# od2_redraw.net
KiCad netlist of a schematic drawn in EAGLE
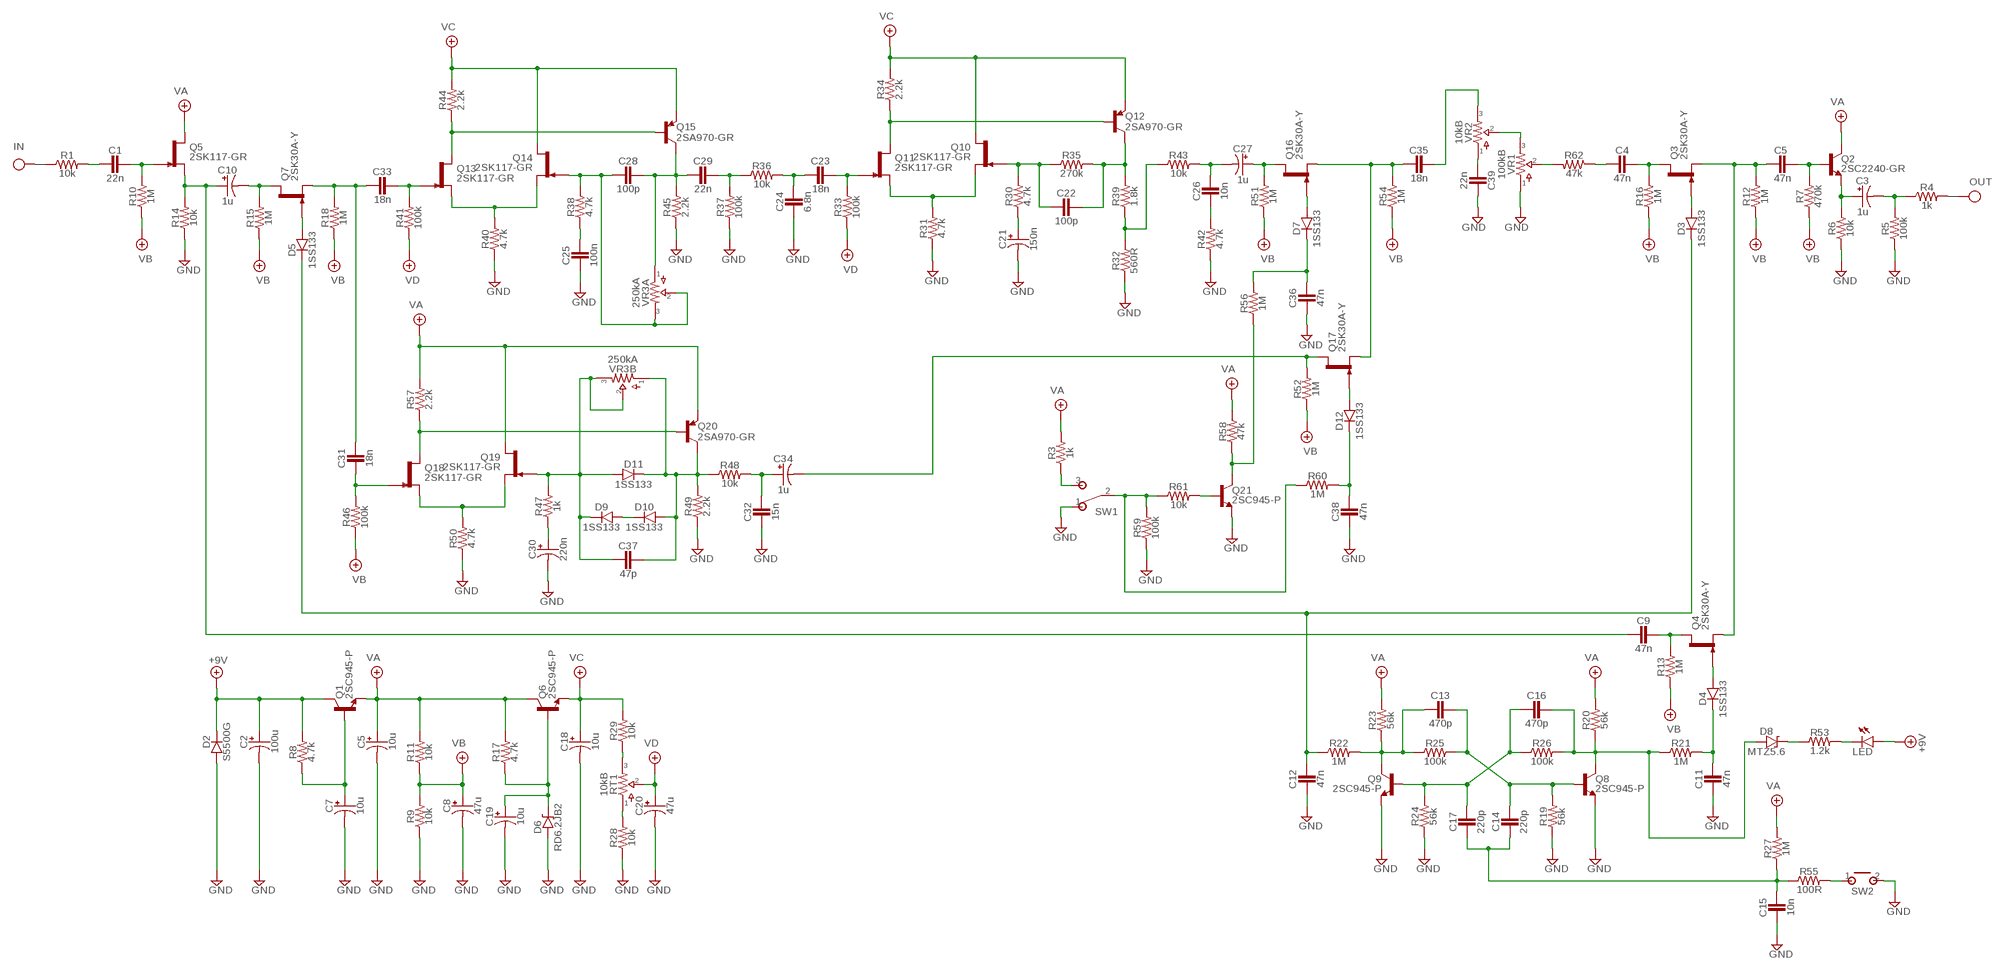
[diagram p0: schematic, sheet 1]

(export (version "E")
  (design (tool "Eeschema 10.0.6"))
  (components
    (comp (ref "C1")
      (value "22n")
      (footprint "eagle-import:BOX_SMALL")
      (libsource (lib "eagle-import") (part "CER/FILMBOX.1"))
    )
    (comp (ref "C2")
      (value "100u")
      (footprint "eagle-import:040_020")
      (libsource (lib "eagle-import") (part "0400"))
    )
    (comp (ref "C3")
      (value "1u")
      (footprint "eagle-import:040_020")
      (libsource (lib "eagle-import") (part "0400"))
    )
    (comp (ref "C4")
      (value "47n")
      (footprint "eagle-import:BOX_SMALL")
      (libsource (lib "eagle-import") (part "CER/FILMBOX.1"))
    )
    (comp (ref "C5")
      (value "10u")
      (footprint "eagle-import:040_020")
      (libsource (lib "eagle-import") (part "0400"))
    )
    (comp (ref "C5 ")
      (value "47n")
      (footprint "eagle-import:BOX_SMALL")
      (libsource (lib "eagle-import") (part "CER/FILMBOX.1"))
    )
    (comp (ref "C7")
      (value "10u")
      (footprint "eagle-import:040_020")
      (libsource (lib "eagle-import") (part "0400"))
    )
    (comp (ref "C8")
      (value "47u")
      (footprint "eagle-import:040_020")
      (libsource (lib "eagle-import") (part "0400"))
    )
    (comp (ref "C9")
      (value "47n")
      (footprint "eagle-import:BOX_SMALL")
      (libsource (lib "eagle-import") (part "CER/FILMBOX.1"))
    )
    (comp (ref "C10")
      (value "1u")
      (footprint "eagle-import:040_020")
      (libsource (lib "eagle-import") (part "0400"))
    )
    (comp (ref "C11")
      (value "47n")
      (footprint "eagle-import:BOX_SMALL")
      (libsource (lib "eagle-import") (part "CER/FILMBOX.1"))
    )
    (comp (ref "C12")
      (value "47n")
      (footprint "eagle-import:BOX_SMALL")
      (libsource (lib "eagle-import") (part "CER/FILMBOX.1"))
    )
    (comp (ref "C13")
      (value "470p")
      (footprint "eagle-import:BOX_SMALL")
      (libsource (lib "eagle-import") (part "CER/FILMBOX.1"))
    )
    (comp (ref "C14")
      (value "220p")
      (footprint "eagle-import:BOX_SMALL")
      (libsource (lib "eagle-import") (part "CER/FILMBOX.1"))
    )
    (comp (ref "C15")
      (value "10n")
      (footprint "eagle-import:BOX_SMALL")
      (libsource (lib "eagle-import") (part "CER/FILMBOX.1"))
    )
    (comp (ref "C16")
      (value "470p")
      (footprint "eagle-import:BOX_SMALL")
      (libsource (lib "eagle-import") (part "CER/FILMBOX.1"))
    )
    (comp (ref "C17")
      (value "220p")
      (footprint "eagle-import:BOX_SMALL")
      (libsource (lib "eagle-import") (part "CER/FILMBOX.1"))
    )
    (comp (ref "C18")
      (value "10u")
      (footprint "eagle-import:040_020")
      (libsource (lib "eagle-import") (part "0400"))
    )
    (comp (ref "C19")
      (value "10u")
      (footprint "eagle-import:040_020")
      (libsource (lib "eagle-import") (part "0400"))
    )
    (comp (ref "C20")
      (value "47u")
      (footprint "eagle-import:040_020")
      (libsource (lib "eagle-import") (part "0400"))
    )
    (comp (ref "C21")
      (value "150n")
      (footprint "eagle-import:040_020")
      (libsource (lib "eagle-import") (part "0400"))
    )
    (comp (ref "C22")
      (value "100p")
      (footprint "eagle-import:BOX_SMALL")
      (libsource (lib "eagle-import") (part "CER/FILMBOX.1"))
    )
    (comp (ref "C23")
      (value "18n")
      (footprint "eagle-import:BOX_SMALL")
      (libsource (lib "eagle-import") (part "CER/FILMBOX.1"))
    )
    (comp (ref "C24")
      (value "6.8n")
      (footprint "eagle-import:BOX_SMALL")
      (libsource (lib "eagle-import") (part "CER/FILMBOX.1"))
    )
    (comp (ref "C25")
      (value "100n")
      (footprint "eagle-import:BOX_SMALL")
      (libsource (lib "eagle-import") (part "CER/FILMBOX.1"))
    )
    (comp (ref "C26")
      (value "10n")
      (footprint "eagle-import:BOX_SMALL")
      (libsource (lib "eagle-import") (part "CER/FILMBOX.1"))
    )
    (comp (ref "C27")
      (value "1u")
      (footprint "eagle-import:040_020")
      (libsource (lib "eagle-import") (part "0400"))
    )
    (comp (ref "C28")
      (value "100p")
      (footprint "eagle-import:BOX_SMALL")
      (libsource (lib "eagle-import") (part "CER/FILMBOX.1"))
    )
    (comp (ref "C29")
      (value "22n")
      (footprint "eagle-import:BOX_SMALL")
      (libsource (lib "eagle-import") (part "CER/FILMBOX.1"))
    )
    (comp (ref "C30")
      (value "220n")
      (footprint "eagle-import:040_020")
      (libsource (lib "eagle-import") (part "0400"))
    )
    (comp (ref "C31")
      (value "18n")
      (footprint "eagle-import:BOX_SMALL")
      (libsource (lib "eagle-import") (part "CER/FILMBOX.1"))
    )
    (comp (ref "C32")
      (value "15n")
      (footprint "eagle-import:BOX_SMALL")
      (libsource (lib "eagle-import") (part "CER/FILMBOX.1"))
    )
    (comp (ref "C33")
      (value "18n")
      (footprint "eagle-import:BOX_SMALL")
      (libsource (lib "eagle-import") (part "CER/FILMBOX.1"))
    )
    (comp (ref "C34")
      (value "1u")
      (footprint "eagle-import:040_020")
      (libsource (lib "eagle-import") (part "0400"))
    )
    (comp (ref "C35")
      (value "18n")
      (footprint "eagle-import:BOX_SMALL")
      (libsource (lib "eagle-import") (part "CER/FILMBOX.1"))
    )
    (comp (ref "C36")
      (value "47n")
      (footprint "eagle-import:BOX_SMALL")
      (libsource (lib "eagle-import") (part "CER/FILMBOX.1"))
    )
    (comp (ref "C37")
      (value "47p")
      (footprint "eagle-import:BOX_SMALL")
      (libsource (lib "eagle-import") (part "CER/FILMBOX.1"))
    )
    (comp (ref "C38")
      (value "47n")
      (footprint "eagle-import:BOX_SMALL")
      (libsource (lib "eagle-import") (part "CER/FILMBOX.1"))
    )
    (comp (ref "C39")
      (value "22n")
      (footprint "eagle-import:BOX_SMALL")
      (libsource (lib "eagle-import") (part "CER/FILMBOX.1"))
    )
    (comp (ref "D2")
      (value "S5500G")
      (footprint "eagle-import:DO35-2")
      (libsource (lib "eagle-import") (part "DO35.2"))
    )
    (comp (ref "D3")
      (value "1SS133")
      (footprint "eagle-import:DO35-2")
      (libsource (lib "eagle-import") (part "DO35.2"))
    )
    (comp (ref "D4")
      (value "1SS133")
      (footprint "eagle-import:DO35-2")
      (libsource (lib "eagle-import") (part "DO35.2"))
    )
    (comp (ref "D5")
      (value "1SS133")
      (footprint "eagle-import:DO35-2")
      (libsource (lib "eagle-import") (part "DO35.2"))
    )
    (comp (ref "D6")
      (value "RD6.2JB2")
      (footprint "eagle-import:DO41-2")
      (libsource (lib "eagle-import") (part "ZENER.2"))
    )
    (comp (ref "D7")
      (value "1SS133")
      (footprint "eagle-import:DO35-2")
      (libsource (lib "eagle-import") (part "DO35.2"))
    )
    (comp (ref "D8")
      (value "MTZ5.6")
      (footprint "eagle-import:DO41-2")
      (libsource (lib "eagle-import") (part "ZENER.2"))
    )
    (comp (ref "D9")
      (value "1SS133")
      (footprint "eagle-import:DO35-2")
      (libsource (lib "eagle-import") (part "DO35.2"))
    )
    (comp (ref "D10")
      (value "1SS133")
      (footprint "eagle-import:DO35-2")
      (libsource (lib "eagle-import") (part "DO35.2"))
    )
    (comp (ref "D11")
      (value "1SS133")
      (footprint "eagle-import:DO35-2")
      (libsource (lib "eagle-import") (part "DO35.2"))
    )
    (comp (ref "D12")
      (value "1SS133")
      (footprint "eagle-import:DO35-2")
      (libsource (lib "eagle-import") (part "DO35.2"))
    )
    (comp (ref "LED")
      (value "LED")
      (footprint "eagle-import:3MM_D")
      (libsource (lib "eagle-import") (part "LED"))
    )
    (comp (ref "Q1")
      (value "2SC945-P")
      (footprint "eagle-import:TO92-")
      (libsource (lib "eagle-import") (part "2SC828A"))
    )
    (comp (ref "Q2")
      (value "2SC2240-GR")
      (footprint "eagle-import:TO92-")
      (libsource (lib "eagle-import") (part "2SC828A"))
    )
    (comp (ref "Q3")
      (value "2SK30A-Y")
      (footprint "eagle-import:TO92-")
      (libsource (lib "eagle-import") (part "2N3819TO-92S"))
    )
    (comp (ref "Q4")
      (value "2SK30A-Y")
      (footprint "eagle-import:TO92-")
      (libsource (lib "eagle-import") (part "2N3819TO-92S"))
    )
    (comp (ref "Q5")
      (value "2SK117-GR")
      (footprint "eagle-import:TO92-")
      (libsource (lib "eagle-import") (part "2N3819TO-92S"))
    )
    (comp (ref "Q6")
      (value "2SC945-P")
      (footprint "eagle-import:TO92-")
      (libsource (lib "eagle-import") (part "2SC828A"))
    )
    (comp (ref "Q7")
      (value "2SK30A-Y")
      (footprint "eagle-import:TO92-")
      (libsource (lib "eagle-import") (part "2N3819TO-92S"))
    )
    (comp (ref "Q8")
      (value "2SC945-P")
      (footprint "eagle-import:TO92-")
      (libsource (lib "eagle-import") (part "2SC828A"))
    )
    (comp (ref "Q9")
      (value "2SC945-P")
      (footprint "eagle-import:TO92-")
      (libsource (lib "eagle-import") (part "2SC828A"))
    )
    (comp (ref "Q10")
      (value "2SK117-GR")
      (footprint "eagle-import:TO92-")
      (libsource (lib "eagle-import") (part "2N3819TO-92S"))
    )
    (comp (ref "Q11")
      (value "2SK117-GR")
      (footprint "eagle-import:TO92-")
      (libsource (lib "eagle-import") (part "2N3819TO-92S"))
    )
    (comp (ref "Q12")
      (value "2SA970-GR")
      (footprint "eagle-import:TO92")
      (libsource (lib "eagle-import") (part "2N3906"))
    )
    (comp (ref "Q13")
      (value "2SK117-GR")
      (footprint "eagle-import:TO92-")
      (libsource (lib "eagle-import") (part "2N3819TO-92S"))
    )
    (comp (ref "Q14")
      (value "2SK117-GR")
      (footprint "eagle-import:TO92-")
      (libsource (lib "eagle-import") (part "2N3819TO-92S"))
    )
    (comp (ref "Q15")
      (value "2SA970-GR")
      (footprint "eagle-import:TO92")
      (libsource (lib "eagle-import") (part "2N3906"))
    )
    (comp (ref "Q16")
      (value "2SK30A-Y")
      (footprint "eagle-import:TO92-")
      (libsource (lib "eagle-import") (part "2N3819TO-92S"))
    )
    (comp (ref "Q17")
      (value "2SK30A-Y")
      (footprint "eagle-import:TO92-")
      (libsource (lib "eagle-import") (part "2N3819TO-92S"))
    )
    (comp (ref "Q18")
      (value "2SK117-GR")
      (footprint "eagle-import:TO92-")
      (libsource (lib "eagle-import") (part "2N3819TO-92S"))
    )
    (comp (ref "Q19")
      (value "2SK117-GR")
      (footprint "eagle-import:TO92-")
      (libsource (lib "eagle-import") (part "2N3819TO-92S"))
    )
    (comp (ref "Q20")
      (value "2SA970-GR")
      (footprint "eagle-import:TO92")
      (libsource (lib "eagle-import") (part "2N3906"))
    )
    (comp (ref "Q21")
      (value "2SC945-P")
      (footprint "eagle-import:TO92-")
      (libsource (lib "eagle-import") (part "2SC828A"))
    )
    (comp (ref "R1")
      (value "10k")
      (footprint "eagle-import:R0207_3")
      (libsource (lib "eagle-import") (part "R_.3B"))
    )
    (comp (ref "R3")
      (value "1k")
      (footprint "eagle-import:R0207_3")
      (libsource (lib "eagle-import") (part "R_.3B"))
    )
    (comp (ref "R4")
      (value "1k")
      (footprint "eagle-import:R0207_3")
      (libsource (lib "eagle-import") (part "R_.3B"))
    )
    (comp (ref "R5")
      (value "100k")
      (footprint "eagle-import:R0207_3")
      (libsource (lib "eagle-import") (part "R_.3B"))
    )
    (comp (ref "R6")
      (value "10k")
      (footprint "eagle-import:R0207_3")
      (libsource (lib "eagle-import") (part "R_.3B"))
    )
    (comp (ref "R7")
      (value "470k")
      (footprint "eagle-import:R0207_3")
      (libsource (lib "eagle-import") (part "R_.3B"))
    )
    (comp (ref "R8")
      (value "4.7k")
      (footprint "eagle-import:R0207_3")
      (libsource (lib "eagle-import") (part "R_.3B"))
    )
    (comp (ref "R9")
      (value "10k")
      (footprint "eagle-import:R0207_3")
      (libsource (lib "eagle-import") (part "R_.3B"))
    )
    (comp (ref "R10")
      (value "1M")
      (footprint "eagle-import:R0207_3")
      (libsource (lib "eagle-import") (part "R_.3B"))
    )
    (comp (ref "R11")
      (value "10k")
      (footprint "eagle-import:R0207_3")
      (libsource (lib "eagle-import") (part "R_.3B"))
    )
    (comp (ref "R12")
      (value "1M")
      (footprint "eagle-import:R0207_3")
      (libsource (lib "eagle-import") (part "R_.3B"))
    )
    (comp (ref "R13")
      (value "1M")
      (footprint "eagle-import:R0207_3")
      (libsource (lib "eagle-import") (part "R_.3B"))
    )
    (comp (ref "R14")
      (value "10k")
      (footprint "eagle-import:R0207_3")
      (libsource (lib "eagle-import") (part "R_.3B"))
    )
    (comp (ref "R15")
      (value "1M")
      (footprint "eagle-import:R0207_3")
      (libsource (lib "eagle-import") (part "R_.3B"))
    )
    (comp (ref "R16")
      (value "1M")
      (footprint "eagle-import:R0207_3")
      (libsource (lib "eagle-import") (part "R_.3B"))
    )
    (comp (ref "R17")
      (value "4.7k")
      (footprint "eagle-import:R0207_3")
      (libsource (lib "eagle-import") (part "R_.3B"))
    )
    (comp (ref "R18")
      (value "1M")
      (footprint "eagle-import:R0207_3")
      (libsource (lib "eagle-import") (part "R_.3B"))
    )
    (comp (ref "R19")
      (value "56k")
      (footprint "eagle-import:R0207_3")
      (libsource (lib "eagle-import") (part "R_.3B"))
    )
    (comp (ref "R20")
      (value "56k")
      (footprint "eagle-import:R0207_3")
      (libsource (lib "eagle-import") (part "R_.3B"))
    )
    (comp (ref "R21")
      (value "1M")
      (footprint "eagle-import:R0207_3")
      (libsource (lib "eagle-import") (part "R_.3B"))
    )
    (comp (ref "R22")
      (value "1M")
      (footprint "eagle-import:R0207_3")
      (libsource (lib "eagle-import") (part "R_.3B"))
    )
    (comp (ref "R23")
      (value "56k")
      (footprint "eagle-import:R0207_3")
      (libsource (lib "eagle-import") (part "R_.3B"))
    )
    (comp (ref "R24")
      (value "56k")
      (footprint "eagle-import:R0207_3")
      (libsource (lib "eagle-import") (part "R_.3B"))
    )
    (comp (ref "R25")
      (value "100k")
      (footprint "eagle-import:R0207_3")
      (libsource (lib "eagle-import") (part "R_.3B"))
    )
    (comp (ref "R26")
      (value "100k")
      (footprint "eagle-import:R0207_3")
      (libsource (lib "eagle-import") (part "R_.3B"))
    )
    (comp (ref "R27")
      (value "1M")
      (footprint "eagle-import:R0207_3")
      (libsource (lib "eagle-import") (part "R_.3B"))
    )
    (comp (ref "R28")
      (value "10k")
      (footprint "eagle-import:R0207_3")
      (libsource (lib "eagle-import") (part "R_.3B"))
    )
    (comp (ref "R29")
      (value "10k")
      (footprint "eagle-import:R0207_3")
      (libsource (lib "eagle-import") (part "R_.3B"))
    )
    (comp (ref "R30")
      (value "4.7k")
      (footprint "eagle-import:R0207_3")
      (libsource (lib "eagle-import") (part "R_.3B"))
    )
    (comp (ref "R31")
      (value "4.7k")
      (footprint "eagle-import:R0207_3")
      (libsource (lib "eagle-import") (part "R_.3B"))
    )
    (comp (ref "R32")
      (value "560R")
      (footprint "eagle-import:R0207_3")
      (libsource (lib "eagle-import") (part "R_.3B"))
    )
    (comp (ref "R33")
      (value "100k")
      (footprint "eagle-import:R0207_3")
      (libsource (lib "eagle-import") (part "R_.3B"))
    )
    (comp (ref "R34")
      (value "2.2k")
      (footprint "eagle-import:R0207_3")
      (libsource (lib "eagle-import") (part "R_.3B"))
    )
    (comp (ref "R35")
      (value "270k")
      (footprint "eagle-import:R0207_3")
      (libsource (lib "eagle-import") (part "R_.3B"))
    )
    (comp (ref "R36")
      (value "10k")
      (footprint "eagle-import:R0207_3")
      (libsource (lib "eagle-import") (part "R_.3B"))
    )
    (comp (ref "R37")
      (value "100k")
      (footprint "eagle-import:R0207_3")
      (libsource (lib "eagle-import") (part "R_.3B"))
    )
    (comp (ref "R38")
      (value "4.7k")
      (footprint "eagle-import:R0207_3")
      (libsource (lib "eagle-import") (part "R_.3B"))
    )
    (comp (ref "R39")
      (value "1.8k")
      (footprint "eagle-import:R0207_3")
      (libsource (lib "eagle-import") (part "R_.3B"))
    )
    (comp (ref "R40")
      (value "4.7k")
      (footprint "eagle-import:R0207_3")
      (libsource (lib "eagle-import") (part "R_.3B"))
    )
    (comp (ref "R41")
      (value "100k")
      (footprint "eagle-import:R0207_3")
      (libsource (lib "eagle-import") (part "R_.3B"))
    )
    (comp (ref "R42")
      (value "4.7k")
      (footprint "eagle-import:R0207_3")
      (libsource (lib "eagle-import") (part "R_.3B"))
    )
    (comp (ref "R43")
      (value "10k")
      (footprint "eagle-import:R0207_3")
      (libsource (lib "eagle-import") (part "R_.3B"))
    )
    (comp (ref "R44")
      (value "2.2k")
      (footprint "eagle-import:R0207_3")
      (libsource (lib "eagle-import") (part "R_.3B"))
    )
    (comp (ref "R45")
      (value "2.2k")
      (footprint "eagle-import:R0207_3")
      (libsource (lib "eagle-import") (part "R_.3B"))
    )
    (comp (ref "R46")
      (value "100k")
      (footprint "eagle-import:R0207_3")
      (libsource (lib "eagle-import") (part "R_.3B"))
    )
    (comp (ref "R47")
      (value "1k")
      (footprint "eagle-import:R0207_3")
      (libsource (lib "eagle-import") (part "R_.3B"))
    )
    (comp (ref "R48")
      (value "10k")
      (footprint "eagle-import:R0207_3")
      (libsource (lib "eagle-import") (part "R_.3B"))
    )
    (comp (ref "R49")
      (value "2.2k")
      (footprint "eagle-import:R0207_3")
      (libsource (lib "eagle-import") (part "R_.3B"))
    )
    (comp (ref "R50")
      (value "4.7k")
      (footprint "eagle-import:R0207_3")
      (libsource (lib "eagle-import") (part "R_.3B"))
    )
    (comp (ref "R51")
      (value "1M")
      (footprint "eagle-import:R0207_3")
      (libsource (lib "eagle-import") (part "R_.3B"))
    )
    (comp (ref "R52")
      (value "1M")
      (footprint "eagle-import:R0207_3")
      (libsource (lib "eagle-import") (part "R_.3B"))
    )
    (comp (ref "R53")
      (value "1.2k")
      (footprint "eagle-import:R0207_3")
      (libsource (lib "eagle-import") (part "R_.3B"))
    )
    (comp (ref "R54")
      (value "1M")
      (footprint "eagle-import:R0207_3")
      (libsource (lib "eagle-import") (part "R_.3B"))
    )
    (comp (ref "R55")
      (value "100R")
      (footprint "eagle-import:R0207_3")
      (libsource (lib "eagle-import") (part "R_.3B"))
    )
    (comp (ref "R56")
      (value "1M")
      (footprint "eagle-import:R0207_3")
      (libsource (lib "eagle-import") (part "R_.3B"))
    )
    (comp (ref "R57")
      (value "2.2k")
      (footprint "eagle-import:R0207_3")
      (libsource (lib "eagle-import") (part "R_.3B"))
    )
    (comp (ref "R58")
      (value "47k")
      (footprint "eagle-import:R0207_3")
      (libsource (lib "eagle-import") (part "R_.3B"))
    )
    (comp (ref "R59")
      (value "100k")
      (footprint "eagle-import:R0207_3")
      (libsource (lib "eagle-import") (part "R_.3B"))
    )
    (comp (ref "R60")
      (value "1M")
      (footprint "eagle-import:R0207_3")
      (libsource (lib "eagle-import") (part "R_.3B"))
    )
    (comp (ref "R61")
      (value "10k")
      (footprint "eagle-import:R0207_3")
      (libsource (lib "eagle-import") (part "R_.3B"))
    )
    (comp (ref "R62")
      (value "47k")
      (footprint "eagle-import:R0207_3")
      (libsource (lib "eagle-import") (part "R_.3B"))
    )
    (comp (ref "RT1")
      (value "10kB")
      (footprint "eagle-import:16MM")
      (libsource (lib "eagle-import") (part "POTS16MM"))
    )
    (comp (ref "SW1")
      (value "SPDT")
      (footprint "eagle-import:M9040P")
      (libsource (lib "eagle-import") (part "SPDT"))
    )
    (comp (ref "SW2")
      (value "MOMENTARY")
      (footprint "eagle-import:SPST")
      (libsource (lib "eagle-import") (part "MOMENTARY"))
    )
    (comp (ref "VR1")
      (value "100kB")
      (footprint "eagle-import:16MM")
      (libsource (lib "eagle-import") (part "POTS16MM"))
    )
    (comp (ref "VR2")
      (value "10kB")
      (footprint "eagle-import:16MM")
      (libsource (lib "eagle-import") (part "POTS16MM"))
    )
    (comp (ref "VR3A")
      (value "250kA")
      (footprint "eagle-import:16MM")
      (libsource (lib "eagle-import") (part "POTS16MM"))
    )
    (comp (ref "VR3B")
      (value "250kA")
      (footprint "eagle-import:16MM")
      (libsource (lib "eagle-import") (part "POTS16MM"))
    )
  )
  (nets
    (net (code "1") (name "+9V") (class "Default")
      (node (ref "C2") (pin "+") (pinfunction "+_+") (pintype "passive"))
      (node (ref "D2") (pin "C") (pinfunction "C_C") (pintype "passive"))
      (node (ref "LED") (pin "ANODE") (pinfunction "A_ANODE") (pintype "passive"))
      (node (ref "Q1") (pin "2") (pinfunction "C_2") (pintype "passive"))
      (node (ref "R8") (pin "2") (pinfunction "2_2") (pintype "passive"))
    )
    (net (code "2") (name "GND") (class "Default")
      (node (ref "C11") (pin "2") (pinfunction "2_2") (pintype "passive"))
      (node (ref "C12") (pin "2") (pinfunction "2_2") (pintype "passive"))
      (node (ref "C15") (pin "2") (pinfunction "2_2") (pintype "passive"))
      (node (ref "C18") (pin "-") (pinfunction "-_-") (pintype "passive"))
      (node (ref "C19") (pin "-") (pinfunction "-_-") (pintype "passive"))
      (node (ref "C2") (pin "-") (pinfunction "-_-") (pintype "passive"))
      (node (ref "C20") (pin "-") (pinfunction "-_-") (pintype "passive"))
      (node (ref "C21") (pin "-") (pinfunction "-_-") (pintype "passive"))
      (node (ref "C24") (pin "2") (pinfunction "2_2") (pintype "passive"))
      (node (ref "C25") (pin "2") (pinfunction "2_2") (pintype "passive"))
      (node (ref "C30") (pin "-") (pinfunction "-_-") (pintype "passive"))
      (node (ref "C32") (pin "2") (pinfunction "2_2") (pintype "passive"))
      (node (ref "C36") (pin "2") (pinfunction "2_2") (pintype "passive"))
      (node (ref "C38") (pin "2") (pinfunction "2_2") (pintype "passive"))
      (node (ref "C39") (pin "2") (pinfunction "2_2") (pintype "passive"))
      (node (ref "C5") (pin "-") (pinfunction "-_-") (pintype "passive"))
      (node (ref "C7") (pin "-") (pinfunction "-_-") (pintype "passive"))
      (node (ref "C8") (pin "-") (pinfunction "-_-") (pintype "passive"))
      (node (ref "D2") (pin "A") (pinfunction "A_A") (pintype "passive"))
      (node (ref "D6") (pin "A") (pinfunction "A_A") (pintype "passive"))
      (node (ref "Q21") (pin "3") (pinfunction "E_3") (pintype "passive"))
      (node (ref "Q8") (pin "3") (pinfunction "E_3") (pintype "passive"))
      (node (ref "Q9") (pin "3") (pinfunction "E_3") (pintype "passive"))
      (node (ref "R14") (pin "1") (pinfunction "1_1") (pintype "passive"))
      (node (ref "R19") (pin "1") (pinfunction "1_1") (pintype "passive"))
      (node (ref "R24") (pin "1") (pinfunction "1_1") (pintype "passive"))
      (node (ref "R28") (pin "1") (pinfunction "1_1") (pintype "passive"))
      (node (ref "R31") (pin "1") (pinfunction "1_1") (pintype "passive"))
      (node (ref "R32") (pin "1") (pinfunction "1_1") (pintype "passive"))
      (node (ref "R37") (pin "1") (pinfunction "1_1") (pintype "passive"))
      (node (ref "R40") (pin "1") (pinfunction "1_1") (pintype "passive"))
      (node (ref "R42") (pin "1") (pinfunction "1_1") (pintype "passive"))
      (node (ref "R45") (pin "1") (pinfunction "1_1") (pintype "passive"))
      (node (ref "R49") (pin "1") (pinfunction "1_1") (pintype "passive"))
      (node (ref "R5") (pin "1") (pinfunction "1_1") (pintype "passive"))
      (node (ref "R50") (pin "1") (pinfunction "1_1") (pintype "passive"))
      (node (ref "R59") (pin "1") (pinfunction "1_1") (pintype "passive"))
      (node (ref "R6") (pin "1") (pinfunction "1_1") (pintype "passive"))
      (node (ref "R9") (pin "1") (pinfunction "1_1") (pintype "passive"))
      (node (ref "SW1") (pin "1") (pinfunction "O_1") (pintype "passive"))
      (node (ref "SW2") (pin "2") (pinfunction "S_2") (pintype "passive"))
      (node (ref "VR1") (pin "1") (pinfunction "1_1") (pintype "passive"))
    )
    (net (code "4") (name "Net-(C1-Pad2)") (class "Default")
      (node (ref "C1") (pin "2") (pinfunction "2_2") (pintype "passive"))
      (node (ref "R1") (pin "2") (pinfunction "2_2") (pintype "passive"))
    )
    (net (code "5") (name "Net-(C3-Pad-)") (class "Default")
      (node (ref "C3") (pin "-") (pinfunction "-_-") (pintype "passive"))
      (node (ref "R4") (pin "1") (pinfunction "1_1") (pintype "passive"))
      (node (ref "R5") (pin "2") (pinfunction "2_2") (pintype "passive"))
    )
    (net (code "6") (name "Net-(C4-Pad2)") (class "Default")
      (node (ref "C4") (pin "2") (pinfunction "2_2") (pintype "passive"))
      (node (ref "R62") (pin "1") (pinfunction "1_1") (pintype "passive"))
    )
    (net (code "7") (name "Net-(C11-Pad1)") (class "Default")
      (node (ref "C11") (pin "1") (pinfunction "1_1") (pintype "passive"))
      (node (ref "D4") (pin "C") (pinfunction "C_C") (pintype "passive"))
      (node (ref "R21") (pin "2") (pinfunction "2_2") (pintype "passive"))
    )
    (net (code "8") (name "Net-(C12-Pad1)") (class "Default")
      (node (ref "C12") (pin "1") (pinfunction "1_1") (pintype "passive"))
      (node (ref "D3") (pin "C") (pinfunction "C_C") (pintype "passive"))
      (node (ref "D5") (pin "C") (pinfunction "C_C") (pintype "passive"))
      (node (ref "R22") (pin "1") (pinfunction "1_1") (pintype "passive"))
    )
    (net (code "9") (name "Net-(C14-Pad2)") (class "Default")
      (node (ref "C14") (pin "2") (pinfunction "2_2") (pintype "passive"))
      (node (ref "C15") (pin "1") (pinfunction "1_1") (pintype "passive"))
      (node (ref "C17") (pin "2") (pinfunction "2_2") (pintype "passive"))
      (node (ref "R27") (pin "1") (pinfunction "1_1") (pintype "passive"))
      (node (ref "R55") (pin "1") (pinfunction "1_1") (pintype "passive"))
    )
    (net (code "10") (name "Net-(C21-Pad+)") (class "Default")
      (node (ref "C21") (pin "+") (pinfunction "+_+") (pintype "passive"))
      (node (ref "R30") (pin "1") (pinfunction "1_1") (pintype "passive"))
    )
    (net (code "11") (name "Net-(C23-Pad2)") (class "Default")
      (node (ref "C23") (pin "2") (pinfunction "2_2") (pintype "passive"))
      (node (ref "C24") (pin "1") (pinfunction "1_1") (pintype "passive"))
      (node (ref "R36") (pin "2") (pinfunction "2_2") (pintype "passive"))
    )
    (net (code "12") (name "Net-(C25-Pad1)") (class "Default")
      (node (ref "C25") (pin "1") (pinfunction "1_1") (pintype "passive"))
      (node (ref "R38") (pin "1") (pinfunction "1_1") (pintype "passive"))
    )
    (net (code "13") (name "Net-(C26-Pad1)") (class "Default")
      (node (ref "C26") (pin "1") (pinfunction "1_1") (pintype "passive"))
      (node (ref "C27") (pin "-") (pinfunction "-_-") (pintype "passive"))
      (node (ref "R43") (pin "2") (pinfunction "2_2") (pintype "passive"))
    )
    (net (code "14") (name "Net-(C26-Pad2)") (class "Default")
      (node (ref "C26") (pin "2") (pinfunction "2_2") (pintype "passive"))
      (node (ref "R42") (pin "2") (pinfunction "2_2") (pintype "passive"))
    )
    (net (code "15") (name "Net-(C29-Pad1)") (class "Default")
      (node (ref "C29") (pin "1") (pinfunction "1_1") (pintype "passive"))
      (node (ref "R36") (pin "1") (pinfunction "1_1") (pintype "passive"))
      (node (ref "R37") (pin "2") (pinfunction "2_2") (pintype "passive"))
    )
    (net (code "16") (name "Net-(C30-Pad+)") (class "Default")
      (node (ref "C30") (pin "+") (pinfunction "+_+") (pintype "passive"))
      (node (ref "R47") (pin "1") (pinfunction "1_1") (pintype "passive"))
    )
    (net (code "17") (name "Net-(C32-Pad1)") (class "Default")
      (node (ref "C32") (pin "1") (pinfunction "1_1") (pintype "passive"))
      (node (ref "C34") (pin "+") (pinfunction "+_+") (pintype "passive"))
      (node (ref "R48") (pin "2") (pinfunction "2_2") (pintype "passive"))
    )
    (net (code "18") (name "Net-(C35-Pad1)") (class "Default")
      (node (ref "C35") (pin "1") (pinfunction "1_1") (pintype "passive"))
      (node (ref "VR2") (pin "3") (pinfunction "3_3") (pintype "passive"))
    )
    (net (code "19") (name "Net-(C36-Pad1)") (class "Default")
      (node (ref "C36") (pin "1") (pinfunction "1_1") (pintype "passive"))
      (node (ref "D7") (pin "C") (pinfunction "C_C") (pintype "passive"))
      (node (ref "R56") (pin "2") (pinfunction "2_2") (pintype "passive"))
    )
    (net (code "20") (name "Net-(C38-Pad1)") (class "Default")
      (node (ref "C38") (pin "1") (pinfunction "1_1") (pintype "passive"))
      (node (ref "D12") (pin "C") (pinfunction "C_C") (pintype "passive"))
      (node (ref "R60") (pin "2") (pinfunction "2_2") (pintype "passive"))
    )
    (net (code "21") (name "Net-(C39-Pad1)") (class "Default")
      (node (ref "C39") (pin "1") (pinfunction "1_1") (pintype "passive"))
      (node (ref "VR2") (pin "1") (pinfunction "1_1") (pintype "passive"))
    )
    (net (code "22") (name "Net-(D8-PadC)") (class "Default")
      (node (ref "D8") (pin "C") (pinfunction "C_C") (pintype "passive"))
      (node (ref "R53") (pin "1") (pinfunction "1_1") (pintype "passive"))
    )
    (net (code "23") (name "Net-(D10-PadC)") (class "Default")
      (node (ref "D10") (pin "C") (pinfunction "C_C") (pintype "passive"))
      (node (ref "D9") (pin "A") (pinfunction "A_A") (pintype "passive"))
    )
    (net (code "24") (name "Net-(LED-C)") (class "Default")
      (node (ref "LED") (pin "P$1") (pinfunction "C_P$1") (pintype "passive"))
      (node (ref "R53") (pin "2") (pinfunction "2_2") (pintype "passive"))
    )
    (net (code "25") (name "Net-(Q1-B)") (class "Default")
      (node (ref "C7") (pin "+") (pinfunction "+_+") (pintype "passive"))
      (node (ref "Q1") (pin "1") (pinfunction "B_1") (pintype "passive"))
      (node (ref "R8") (pin "1") (pinfunction "1_1") (pintype "passive"))
    )
    (net (code "26") (name "Net-(Q2-B)") (class "Default")
      (node (ref "C5 ") (pin "1") (pinfunction "1_1") (pintype "passive"))
      (node (ref "Q2") (pin "1") (pinfunction "B_1") (pintype "passive"))
      (node (ref "R7") (pin "2") (pinfunction "2_2") (pintype "passive"))
    )
    (net (code "27") (name "Net-(Q2-E)") (class "Default")
      (node (ref "C3") (pin "+") (pinfunction "+_+") (pintype "passive"))
      (node (ref "Q2") (pin "3") (pinfunction "E_3") (pintype "passive"))
      (node (ref "R6") (pin "2") (pinfunction "2_2") (pintype "passive"))
    )
    (net (code "28") (name "Net-(Q3-D)") (class "Default")
      (node (ref "C4") (pin "1") (pinfunction "1_1") (pintype "passive"))
      (node (ref "Q3") (pin "3") (pinfunction "D_3") (pintype "passive"))
      (node (ref "R16") (pin "2") (pinfunction "2_2") (pintype "passive"))
    )
    (net (code "29") (name "Net-(Q3-G)") (class "Default")
      (node (ref "D3") (pin "A") (pinfunction "A_A") (pintype "passive"))
      (node (ref "Q3") (pin "2") (pinfunction "G_2") (pintype "passive"))
    )
    (net (code "30") (name "Net-(Q3-S)") (class "Default")
      (node (ref "C5 ") (pin "2") (pinfunction "2_2") (pintype "passive"))
      (node (ref "Q3") (pin "1") (pinfunction "S_1") (pintype "passive"))
      (node (ref "Q4") (pin "1") (pinfunction "S_1") (pintype "passive"))
      (node (ref "R12") (pin "2") (pinfunction "2_2") (pintype "passive"))
    )
    (net (code "31") (name "Net-(Q4-D)") (class "Default")
      (node (ref "C9") (pin "1") (pinfunction "1_1") (pintype "passive"))
      (node (ref "Q4") (pin "3") (pinfunction "D_3") (pintype "passive"))
      (node (ref "R13") (pin "2") (pinfunction "2_2") (pintype "passive"))
    )
    (net (code "32") (name "Net-(Q4-G)") (class "Default")
      (node (ref "D4") (pin "A") (pinfunction "A_A") (pintype "passive"))
      (node (ref "Q4") (pin "2") (pinfunction "G_2") (pintype "passive"))
    )
    (net (code "33") (name "Net-(Q5-G)") (class "Default")
      (node (ref "C1") (pin "1") (pinfunction "1_1") (pintype "passive"))
      (node (ref "Q5") (pin "2") (pinfunction "G_2") (pintype "passive"))
      (node (ref "R10") (pin "2") (pinfunction "2_2") (pintype "passive"))
    )
    (net (code "34") (name "Net-(Q5-S)") (class "Default")
      (node (ref "C10") (pin "+") (pinfunction "+_+") (pintype "passive"))
      (node (ref "C9") (pin "2") (pinfunction "2_2") (pintype "passive"))
      (node (ref "Q5") (pin "1") (pinfunction "S_1") (pintype "passive"))
      (node (ref "R14") (pin "2") (pinfunction "2_2") (pintype "passive"))
    )
    (net (code "35") (name "Net-(Q6-B)") (class "Default")
      (node (ref "C19") (pin "+") (pinfunction "+_+") (pintype "passive"))
      (node (ref "D6") (pin "C") (pinfunction "C_C") (pintype "passive"))
      (node (ref "Q6") (pin "1") (pinfunction "B_1") (pintype "passive"))
      (node (ref "R17") (pin "1") (pinfunction "1_1") (pintype "passive"))
    )
    (net (code "36") (name "Net-(Q7-D)") (class "Default")
      (node (ref "C10") (pin "-") (pinfunction "-_-") (pintype "passive"))
      (node (ref "Q7") (pin "3") (pinfunction "D_3") (pintype "passive"))
      (node (ref "R15") (pin "2") (pinfunction "2_2") (pintype "passive"))
    )
    (net (code "37") (name "Net-(Q7-G)") (class "Default")
      (node (ref "D5") (pin "A") (pinfunction "A_A") (pintype "passive"))
      (node (ref "Q7") (pin "2") (pinfunction "G_2") (pintype "passive"))
    )
    (net (code "38") (name "Net-(Q7-S)") (class "Default")
      (node (ref "C31") (pin "1") (pinfunction "1_1") (pintype "passive"))
      (node (ref "C33") (pin "2") (pinfunction "2_2") (pintype "passive"))
      (node (ref "Q7") (pin "1") (pinfunction "S_1") (pintype "passive"))
      (node (ref "R18") (pin "2") (pinfunction "2_2") (pintype "passive"))
    )
    (net (code "39") (name "Net-(Q8-B)") (class "Default")
      (node (ref "C13") (pin "1") (pinfunction "1_1") (pintype "passive"))
      (node (ref "C14") (pin "1") (pinfunction "1_1") (pintype "passive"))
      (node (ref "Q8") (pin "1") (pinfunction "B_1") (pintype "passive"))
      (node (ref "R19") (pin "2") (pinfunction "2_2") (pintype "passive"))
      (node (ref "R25") (pin "2") (pinfunction "2_2") (pintype "passive"))
    )
    (net (code "40") (name "Net-(Q8-C)") (class "Default")
      (node (ref "C16") (pin "1") (pinfunction "1_1") (pintype "passive"))
      (node (ref "D8") (pin "A") (pinfunction "A_A") (pintype "passive"))
      (node (ref "Q8") (pin "2") (pinfunction "C_2") (pintype "passive"))
      (node (ref "R20") (pin "1") (pinfunction "1_1") (pintype "passive"))
      (node (ref "R21") (pin "1") (pinfunction "1_1") (pintype "passive"))
      (node (ref "R26") (pin "2") (pinfunction "2_2") (pintype "passive"))
    )
    (net (code "41") (name "Net-(Q9-B)") (class "Default")
      (node (ref "C16") (pin "2") (pinfunction "2_2") (pintype "passive"))
      (node (ref "C17") (pin "1") (pinfunction "1_1") (pintype "passive"))
      (node (ref "Q9") (pin "1") (pinfunction "B_1") (pintype "passive"))
      (node (ref "R24") (pin "2") (pinfunction "2_2") (pintype "passive"))
      (node (ref "R26") (pin "1") (pinfunction "1_1") (pintype "passive"))
    )
    (net (code "42") (name "Net-(Q9-C)") (class "Default")
      (node (ref "C13") (pin "2") (pinfunction "2_2") (pintype "passive"))
      (node (ref "Q9") (pin "2") (pinfunction "C_2") (pintype "passive"))
      (node (ref "R22") (pin "2") (pinfunction "2_2") (pintype "passive"))
      (node (ref "R23") (pin "1") (pinfunction "1_1") (pintype "passive"))
      (node (ref "R25") (pin "1") (pinfunction "1_1") (pintype "passive"))
    )
    (net (code "43") (name "Net-(Q10-G)") (class "Default")
      (node (ref "C22") (pin "2") (pinfunction "2_2") (pintype "passive"))
      (node (ref "Q10") (pin "2") (pinfunction "G_2") (pintype "passive"))
      (node (ref "R30") (pin "2") (pinfunction "2_2") (pintype "passive"))
      (node (ref "R35") (pin "1") (pinfunction "1_1") (pintype "passive"))
    )
    (net (code "44") (name "Net-(Q10-S)") (class "Default")
      (node (ref "Q10") (pin "1") (pinfunction "S_1") (pintype "passive"))
      (node (ref "Q11") (pin "1") (pinfunction "S_1") (pintype "passive"))
      (node (ref "R31") (pin "2") (pinfunction "2_2") (pintype "passive"))
    )
    (net (code "45") (name "Net-(Q11-D)") (class "Default")
      (node (ref "Q11") (pin "3") (pinfunction "D_3") (pintype "passive"))
      (node (ref "Q12") (pin "2") (pinfunction "B_2") (pintype "passive"))
      (node (ref "R34") (pin "1") (pinfunction "1_1") (pintype "passive"))
    )
    (net (code "46") (name "Net-(Q11-G)") (class "Default")
      (node (ref "C23") (pin "1") (pinfunction "1_1") (pintype "passive"))
      (node (ref "Q11") (pin "2") (pinfunction "G_2") (pintype "passive"))
      (node (ref "R33") (pin "2") (pinfunction "2_2") (pintype "passive"))
    )
    (net (code "47") (name "Net-(Q12-C)") (class "Default")
      (node (ref "C22") (pin "1") (pinfunction "1_1") (pintype "passive"))
      (node (ref "Q12") (pin "1") (pinfunction "C_1") (pintype "passive"))
      (node (ref "R35") (pin "2") (pinfunction "2_2") (pintype "passive"))
      (node (ref "R39") (pin "2") (pinfunction "2_2") (pintype "passive"))
    )
    (net (code "48") (name "Net-(Q13-D)") (class "Default")
      (node (ref "Q13") (pin "3") (pinfunction "D_3") (pintype "passive"))
      (node (ref "Q15") (pin "2") (pinfunction "B_2") (pintype "passive"))
      (node (ref "R44") (pin "1") (pinfunction "1_1") (pintype "passive"))
    )
    (net (code "49") (name "Net-(Q13-G)") (class "Default")
      (node (ref "C33") (pin "1") (pinfunction "1_1") (pintype "passive"))
      (node (ref "Q13") (pin "2") (pinfunction "G_2") (pintype "passive"))
      (node (ref "R41") (pin "2") (pinfunction "2_2") (pintype "passive"))
    )
    (net (code "50") (name "Net-(Q13-S)") (class "Default")
      (node (ref "Q13") (pin "1") (pinfunction "S_1") (pintype "passive"))
      (node (ref "Q14") (pin "1") (pinfunction "S_1") (pintype "passive"))
      (node (ref "R40") (pin "2") (pinfunction "2_2") (pintype "passive"))
    )
    (net (code "51") (name "Net-(Q14-G)") (class "Default")
      (node (ref "C28") (pin "2") (pinfunction "2_2") (pintype "passive"))
      (node (ref "Q14") (pin "2") (pinfunction "G_2") (pintype "passive"))
      (node (ref "R38") (pin "2") (pinfunction "2_2") (pintype "passive"))
      (node (ref "VR3A") (pin "2") (pinfunction "2_2") (pintype "passive"))
      (node (ref "VR3A") (pin "3") (pinfunction "3_3") (pintype "passive"))
    )
    (net (code "52") (name "Net-(Q15-C)") (class "Default")
      (node (ref "C28") (pin "1") (pinfunction "1_1") (pintype "passive"))
      (node (ref "C29") (pin "2") (pinfunction "2_2") (pintype "passive"))
      (node (ref "Q15") (pin "1") (pinfunction "C_1") (pintype "passive"))
      (node (ref "R45") (pin "2") (pinfunction "2_2") (pintype "passive"))
      (node (ref "VR3A") (pin "1") (pinfunction "1_1") (pintype "passive"))
    )
    (net (code "53") (name "Net-(Q16-D)") (class "Default")
      (node (ref "C27") (pin "+") (pinfunction "+_+") (pintype "passive"))
      (node (ref "Q16") (pin "3") (pinfunction "D_3") (pintype "passive"))
      (node (ref "R51") (pin "2") (pinfunction "2_2") (pintype "passive"))
    )
    (net (code "54") (name "Net-(Q16-G)") (class "Default")
      (node (ref "D7") (pin "A") (pinfunction "A_A") (pintype "passive"))
      (node (ref "Q16") (pin "2") (pinfunction "G_2") (pintype "passive"))
    )
    (net (code "55") (name "Net-(Q16-S)") (class "Default")
      (node (ref "C35") (pin "2") (pinfunction "2_2") (pintype "passive"))
      (node (ref "Q16") (pin "1") (pinfunction "S_1") (pintype "passive"))
      (node (ref "Q17") (pin "1") (pinfunction "S_1") (pintype "passive"))
      (node (ref "R54") (pin "2") (pinfunction "2_2") (pintype "passive"))
    )
    (net (code "56") (name "Net-(Q17-D)") (class "Default")
      (node (ref "C34") (pin "-") (pinfunction "-_-") (pintype "passive"))
      (node (ref "Q17") (pin "3") (pinfunction "D_3") (pintype "passive"))
      (node (ref "R52") (pin "2") (pinfunction "2_2") (pintype "passive"))
    )
    (net (code "57") (name "Net-(Q17-G)") (class "Default")
      (node (ref "D12") (pin "A") (pinfunction "A_A") (pintype "passive"))
      (node (ref "Q17") (pin "2") (pinfunction "G_2") (pintype "passive"))
    )
    (net (code "58") (name "Net-(Q18-D)") (class "Default")
      (node (ref "Q18") (pin "3") (pinfunction "D_3") (pintype "passive"))
      (node (ref "Q20") (pin "2") (pinfunction "B_2") (pintype "passive"))
      (node (ref "R57") (pin "1") (pinfunction "1_1") (pintype "passive"))
    )
    (net (code "59") (name "Net-(Q18-G)") (class "Default")
      (node (ref "C31") (pin "2") (pinfunction "2_2") (pintype "passive"))
      (node (ref "Q18") (pin "2") (pinfunction "G_2") (pintype "passive"))
      (node (ref "R46") (pin "2") (pinfunction "2_2") (pintype "passive"))
    )
    (net (code "60") (name "Net-(Q18-S)") (class "Default")
      (node (ref "Q18") (pin "1") (pinfunction "S_1") (pintype "passive"))
      (node (ref "Q19") (pin "1") (pinfunction "S_1") (pintype "passive"))
      (node (ref "R50") (pin "2") (pinfunction "2_2") (pintype "passive"))
    )
    (net (code "61") (name "Net-(Q19-G)") (class "Default")
      (node (ref "C37") (pin "2") (pinfunction "2_2") (pintype "passive"))
      (node (ref "D11") (pin "A") (pinfunction "A_A") (pintype "passive"))
      (node (ref "D9") (pin "C") (pinfunction "C_C") (pintype "passive"))
      (node (ref "Q19") (pin "2") (pinfunction "G_2") (pintype "passive"))
      (node (ref "R47") (pin "2") (pinfunction "2_2") (pintype "passive"))
      (node (ref "VR3B") (pin "2") (pinfunction "2_2") (pintype "passive"))
      (node (ref "VR3B") (pin "3") (pinfunction "3_3") (pintype "passive"))
    )
    (net (code "62") (name "Net-(Q20-C)") (class "Default")
      (node (ref "C37") (pin "1") (pinfunction "1_1") (pintype "passive"))
      (node (ref "D10") (pin "A") (pinfunction "A_A") (pintype "passive"))
      (node (ref "D11") (pin "C") (pinfunction "C_C") (pintype "passive"))
      (node (ref "Q20") (pin "1") (pinfunction "C_1") (pintype "passive"))
      (node (ref "R48") (pin "1") (pinfunction "1_1") (pintype "passive"))
      (node (ref "R49") (pin "2") (pinfunction "2_2") (pintype "passive"))
      (node (ref "VR3B") (pin "1") (pinfunction "1_1") (pintype "passive"))
    )
    (net (code "63") (name "Net-(Q21-B)") (class "Default")
      (node (ref "Q21") (pin "1") (pinfunction "B_1") (pintype "passive"))
      (node (ref "R61") (pin "2") (pinfunction "2_2") (pintype "passive"))
    )
    (net (code "64") (name "Net-(Q21-C)") (class "Default")
      (node (ref "Q21") (pin "2") (pinfunction "C_2") (pintype "passive"))
      (node (ref "R56") (pin "1") (pinfunction "1_1") (pintype "passive"))
      (node (ref "R58") (pin "1") (pinfunction "1_1") (pintype "passive"))
    )
    (net (code "65") (name "Net-(R28-Pad2)") (class "Default")
      (node (ref "R28") (pin "2") (pinfunction "2_2") (pintype "passive"))
      (node (ref "RT1") (pin "1") (pinfunction "1_1") (pintype "passive"))
    )
    (net (code "66") (name "Net-(R29-Pad1)") (class "Default")
      (node (ref "R29") (pin "1") (pinfunction "1_1") (pintype "passive"))
      (node (ref "RT1") (pin "3") (pinfunction "3_3") (pintype "passive"))
    )
    (net (code "67") (name "Net-(R32-Pad2)") (class "Default")
      (node (ref "R32") (pin "2") (pinfunction "2_2") (pintype "passive"))
      (node (ref "R39") (pin "1") (pinfunction "1_1") (pintype "passive"))
      (node (ref "R43") (pin "1") (pinfunction "1_1") (pintype "passive"))
    )
    (net (code "68") (name "Net-(R62-Pad2)") (class "Default")
      (node (ref "R62") (pin "2") (pinfunction "2_2") (pintype "passive"))
      (node (ref "VR1") (pin "2") (pinfunction "2_2") (pintype "passive"))
    )
    (net (code "69") (name "Net-(SW1-P)") (class "Default")
      (node (ref "R59") (pin "2") (pinfunction "2_2") (pintype "passive"))
      (node (ref "R60") (pin "1") (pinfunction "1_1") (pintype "passive"))
      (node (ref "R61") (pin "1") (pinfunction "1_1") (pintype "passive"))
      (node (ref "SW1") (pin "2") (pinfunction "P_2") (pintype "passive"))
    )
    (net (code "70") (name "Net-(SW1-S)") (class "Default")
      (node (ref "R3") (pin "1") (pinfunction "1_1") (pintype "passive"))
      (node (ref "SW1") (pin "3") (pinfunction "S_3") (pintype "passive"))
    )
    (net (code "71") (name "Net-(SW2-P)") (class "Default")
      (node (ref "R55") (pin "2") (pinfunction "2_2") (pintype "passive"))
      (node (ref "SW2") (pin "1") (pinfunction "P_1") (pintype "passive"))
    )
    (net (code "72") (name "Net-(VR1-Pad3)") (class "Default")
      (node (ref "VR1") (pin "3") (pinfunction "3_3") (pintype "passive"))
      (node (ref "VR2") (pin "2") (pinfunction "2_2") (pintype "passive"))
    )
    (net (code "74") (name "VA") (class "Default")
      (node (ref "C5") (pin "+") (pinfunction "+_+") (pintype "passive"))
      (node (ref "Q1") (pin "3") (pinfunction "E_3") (pintype "passive"))
      (node (ref "Q19") (pin "3") (pinfunction "D_3") (pintype "passive"))
      (node (ref "Q2") (pin "2") (pinfunction "C_2") (pintype "passive"))
      (node (ref "Q20") (pin "3") (pinfunction "E_3") (pintype "passive"))
      (node (ref "Q5") (pin "3") (pinfunction "D_3") (pintype "passive"))
      (node (ref "Q6") (pin "2") (pinfunction "C_2") (pintype "passive"))
      (node (ref "R11") (pin "2") (pinfunction "2_2") (pintype "passive"))
      (node (ref "R17") (pin "2") (pinfunction "2_2") (pintype "passive"))
      (node (ref "R20") (pin "2") (pinfunction "2_2") (pintype "passive"))
      (node (ref "R23") (pin "2") (pinfunction "2_2") (pintype "passive"))
      (node (ref "R27") (pin "2") (pinfunction "2_2") (pintype "passive"))
      (node (ref "R3") (pin "2") (pinfunction "2_2") (pintype "passive"))
      (node (ref "R57") (pin "2") (pinfunction "2_2") (pintype "passive"))
      (node (ref "R58") (pin "2") (pinfunction "2_2") (pintype "passive"))
    )
    (net (code "75") (name "VB") (class "Default")
      (node (ref "C8") (pin "+") (pinfunction "+_+") (pintype "passive"))
      (node (ref "R10") (pin "1") (pinfunction "1_1") (pintype "passive"))
      (node (ref "R11") (pin "1") (pinfunction "1_1") (pintype "passive"))
      (node (ref "R12") (pin "1") (pinfunction "1_1") (pintype "passive"))
      (node (ref "R13") (pin "1") (pinfunction "1_1") (pintype "passive"))
      (node (ref "R15") (pin "1") (pinfunction "1_1") (pintype "passive"))
      (node (ref "R16") (pin "1") (pinfunction "1_1") (pintype "passive"))
      (node (ref "R18") (pin "1") (pinfunction "1_1") (pintype "passive"))
      (node (ref "R46") (pin "1") (pinfunction "1_1") (pintype "passive"))
      (node (ref "R51") (pin "1") (pinfunction "1_1") (pintype "passive"))
      (node (ref "R52") (pin "1") (pinfunction "1_1") (pintype "passive"))
      (node (ref "R54") (pin "1") (pinfunction "1_1") (pintype "passive"))
      (node (ref "R7") (pin "1") (pinfunction "1_1") (pintype "passive"))
      (node (ref "R9") (pin "2") (pinfunction "2_2") (pintype "passive"))
    )
    (net (code "76") (name "VC") (class "Default")
      (node (ref "C18") (pin "+") (pinfunction "+_+") (pintype "passive"))
      (node (ref "Q10") (pin "3") (pinfunction "D_3") (pintype "passive"))
      (node (ref "Q12") (pin "3") (pinfunction "E_3") (pintype "passive"))
      (node (ref "Q14") (pin "3") (pinfunction "D_3") (pintype "passive"))
      (node (ref "Q15") (pin "3") (pinfunction "E_3") (pintype "passive"))
      (node (ref "Q6") (pin "3") (pinfunction "E_3") (pintype "passive"))
      (node (ref "R29") (pin "2") (pinfunction "2_2") (pintype "passive"))
      (node (ref "R34") (pin "2") (pinfunction "2_2") (pintype "passive"))
      (node (ref "R44") (pin "2") (pinfunction "2_2") (pintype "passive"))
    )
    (net (code "77") (name "VD") (class "Default")
      (node (ref "C20") (pin "+") (pinfunction "+_+") (pintype "passive"))
      (node (ref "R33") (pin "1") (pinfunction "1_1") (pintype "passive"))
      (node (ref "R41") (pin "1") (pinfunction "1_1") (pintype "passive"))
      (node (ref "RT1") (pin "2") (pinfunction "2_2") (pintype "passive"))
    )
    (net (code "78") (name "unconnected-(R1-Pad1)") (class "Default")
      (node (ref "R1") (pin "1") (pinfunction "1_1") (pintype "passive"))
    )
    (net (code "79") (name "unconnected-(R4-Pad2)") (class "Default")
      (node (ref "R4") (pin "2") (pinfunction "2_2") (pintype "passive"))
    )
  )
)
